# KeyInput_ABH.net
KiCad netlist of a schematic drawn in Altium Designer
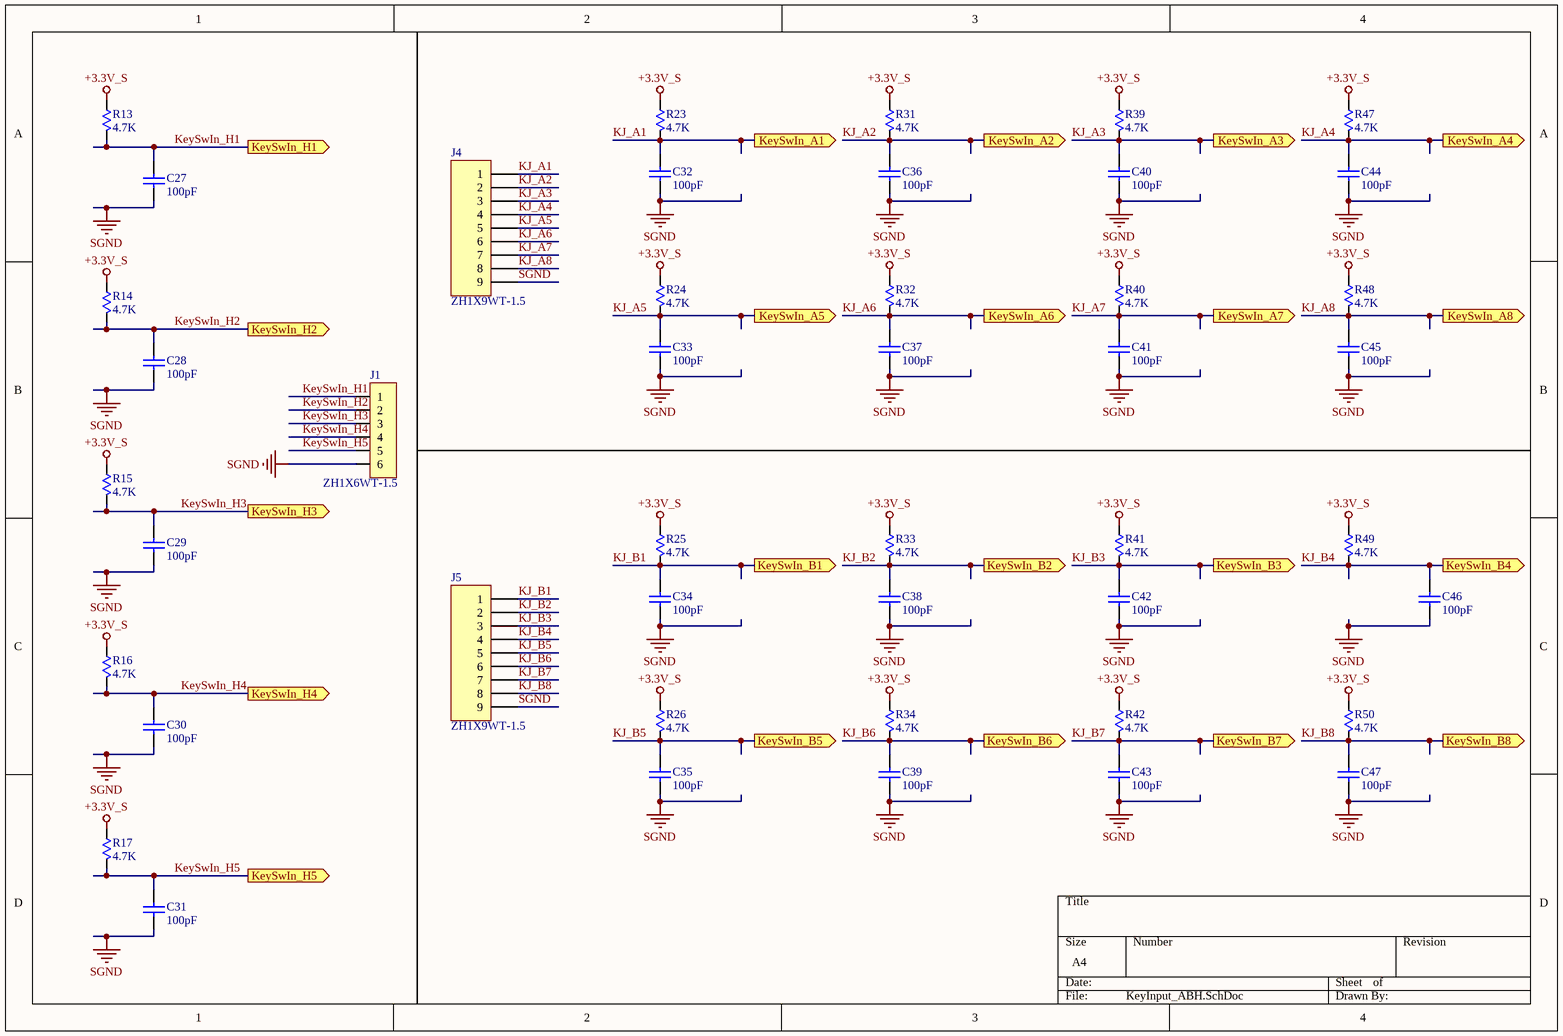
[diagram p0: KeyInput_ABH.SchDoc]

(export (version "E")
  (design (tool "Eeschema 10.0.6"))
  (components
    (comp (ref "C27")
      (value "100pF")
      (footprint "C0805")
      (description "Capacitor")
      (fields (field (name "PUBLISHER") "Altium Limited"))
      (libsource (lib "Miscellaneous Devices") (part "Cap"))
    )
    (comp (ref "C28")
      (value "100pF")
      (footprint "C0805")
      (description "Capacitor")
      (fields (field (name "PUBLISHER") "Altium Limited"))
      (libsource (lib "Miscellaneous Devices") (part "Cap"))
    )
    (comp (ref "C29")
      (value "100pF")
      (footprint "C0805")
      (description "Capacitor")
      (fields (field (name "PUBLISHER") "Altium Limited"))
      (libsource (lib "Miscellaneous Devices") (part "Cap"))
    )
    (comp (ref "C30")
      (value "100pF")
      (footprint "C0805")
      (description "Capacitor")
      (fields (field (name "PUBLISHER") "Altium Limited"))
      (libsource (lib "Miscellaneous Devices") (part "Cap"))
    )
    (comp (ref "C31")
      (value "100pF")
      (footprint "C0805")
      (description "Capacitor")
      (fields (field (name "PUBLISHER") "Altium Limited"))
      (libsource (lib "Miscellaneous Devices") (part "Cap"))
    )
    (comp (ref "C32")
      (value "100pF")
      (footprint "C0805")
      (description "Capacitor")
      (fields (field (name "PUBLISHER") "Altium Limited"))
      (libsource (lib "Miscellaneous Devices") (part "Cap"))
    )
    (comp (ref "C33")
      (value "100pF")
      (footprint "C0805")
      (description "Capacitor")
      (fields (field (name "PUBLISHER") "Altium Limited"))
      (libsource (lib "Miscellaneous Devices") (part "Cap"))
    )
    (comp (ref "C34")
      (value "100pF")
      (footprint "C0805")
      (description "Capacitor")
      (fields (field (name "PUBLISHER") "Altium Limited"))
      (libsource (lib "Miscellaneous Devices") (part "Cap"))
    )
    (comp (ref "C35")
      (value "100pF")
      (footprint "C0805")
      (description "Capacitor")
      (fields (field (name "PUBLISHER") "Altium Limited"))
      (libsource (lib "Miscellaneous Devices") (part "Cap"))
    )
    (comp (ref "C36")
      (value "100pF")
      (footprint "C0805")
      (description "Capacitor")
      (fields (field (name "PUBLISHER") "Altium Limited"))
      (libsource (lib "Miscellaneous Devices") (part "Cap"))
    )
    (comp (ref "C37")
      (value "100pF")
      (footprint "C0805")
      (description "Capacitor")
      (fields (field (name "PUBLISHER") "Altium Limited"))
      (libsource (lib "Miscellaneous Devices") (part "Cap"))
    )
    (comp (ref "C38")
      (value "100pF")
      (footprint "C0805")
      (description "Capacitor")
      (fields (field (name "PUBLISHER") "Altium Limited"))
      (libsource (lib "Miscellaneous Devices") (part "Cap"))
    )
    (comp (ref "C39")
      (value "100pF")
      (footprint "C0805")
      (description "Capacitor")
      (fields (field (name "PUBLISHER") "Altium Limited"))
      (libsource (lib "Miscellaneous Devices") (part "Cap"))
    )
    (comp (ref "C40")
      (value "100pF")
      (footprint "C0805")
      (description "Capacitor")
      (fields (field (name "PUBLISHER") "Altium Limited"))
      (libsource (lib "Miscellaneous Devices") (part "Cap"))
    )
    (comp (ref "C41")
      (value "100pF")
      (footprint "C0805")
      (description "Capacitor")
      (fields (field (name "PUBLISHER") "Altium Limited"))
      (libsource (lib "Miscellaneous Devices") (part "Cap"))
    )
    (comp (ref "C42")
      (value "100pF")
      (footprint "C0805")
      (description "Capacitor")
      (fields (field (name "PUBLISHER") "Altium Limited"))
      (libsource (lib "Miscellaneous Devices") (part "Cap"))
    )
    (comp (ref "C43")
      (value "100pF")
      (footprint "C0805")
      (description "Capacitor")
      (fields (field (name "PUBLISHER") "Altium Limited"))
      (libsource (lib "Miscellaneous Devices") (part "Cap"))
    )
    (comp (ref "C44")
      (value "100pF")
      (footprint "C0805")
      (description "Capacitor")
      (fields (field (name "PUBLISHER") "Altium Limited"))
      (libsource (lib "Miscellaneous Devices") (part "Cap"))
    )
    (comp (ref "C45")
      (value "100pF")
      (footprint "C0805")
      (description "Capacitor")
      (fields (field (name "PUBLISHER") "Altium Limited"))
      (libsource (lib "Miscellaneous Devices") (part "Cap"))
    )
    (comp (ref "C46")
      (value "100pF")
      (footprint "C0805")
      (description "Capacitor")
      (fields (field (name "PUBLISHER") "Altium Limited"))
      (libsource (lib "Miscellaneous Devices") (part "Cap"))
    )
    (comp (ref "C47")
      (value "100pF")
      (footprint "C0805")
      (description "Capacitor")
      (fields (field (name "PUBLISHER") "Altium Limited"))
      (libsource (lib "Miscellaneous Devices") (part "Cap"))
    )
    (comp (ref "J1")
      (value "ZH1X6WT-1.5")
      (footprint "ZH1X6WT-1.5")
      (libsource (lib "Connector Class") (part "HEADER1X6"))
    )
    (comp (ref "J4")
      (value "ZH1X9WT-1.5")
      (footprint "ZH1X9WT-1.5")
      (description "Header, 9-Pin")
      (fields (field (name "PUBLISHER") "Altium Limited"))
      (libsource (lib "Miscellaneous Connectors") (part "Header 9"))
    )
    (comp (ref "J5")
      (value "ZH1X9WT-1.5")
      (footprint "ZH1X9WT-1.5")
      (description "Header, 9-Pin")
      (fields (field (name "PUBLISHER") "Altium Limited"))
      (libsource (lib "Miscellaneous Connectors") (part "Header 9"))
    )
    (comp (ref "R13")
      (value "4.7K")
      (footprint "R0805")
      (description "Resistor")
      (fields (field (name "PUBLISHER") "Altium Limited"))
      (libsource (lib "Passive Components Class") (part "RES"))
    )
    (comp (ref "R14")
      (value "4.7K")
      (footprint "R0805")
      (description "Resistor")
      (fields (field (name "PUBLISHER") "Altium Limited"))
      (libsource (lib "Passive Components Class") (part "RES"))
    )
    (comp (ref "R15")
      (value "4.7K")
      (footprint "R0805")
      (description "Resistor")
      (fields (field (name "PUBLISHER") "Altium Limited"))
      (libsource (lib "Passive Components Class") (part "RES"))
    )
    (comp (ref "R16")
      (value "4.7K")
      (footprint "R0805")
      (description "Resistor")
      (fields (field (name "PUBLISHER") "Altium Limited"))
      (libsource (lib "Passive Components Class") (part "RES"))
    )
    (comp (ref "R17")
      (value "4.7K")
      (footprint "R0805")
      (description "Resistor")
      (fields (field (name "PUBLISHER") "Altium Limited"))
      (libsource (lib "Passive Components Class") (part "RES"))
    )
    (comp (ref "R23")
      (value "4.7K")
      (footprint "R0805")
      (description "Resistor")
      (fields (field (name "PUBLISHER") "Altium Limited"))
      (libsource (lib "Passive Components Class") (part "RES"))
    )
    (comp (ref "R24")
      (value "4.7K")
      (footprint "R0805")
      (description "Resistor")
      (fields (field (name "PUBLISHER") "Altium Limited"))
      (libsource (lib "Passive Components Class") (part "RES"))
    )
    (comp (ref "R25")
      (value "4.7K")
      (footprint "R0805")
      (description "Resistor")
      (fields (field (name "PUBLISHER") "Altium Limited"))
      (libsource (lib "Passive Components Class") (part "RES"))
    )
    (comp (ref "R26")
      (value "4.7K")
      (footprint "R0805")
      (description "Resistor")
      (fields (field (name "PUBLISHER") "Altium Limited"))
      (libsource (lib "Passive Components Class") (part "RES"))
    )
    (comp (ref "R31")
      (value "4.7K")
      (footprint "R0805")
      (description "Resistor")
      (fields (field (name "PUBLISHER") "Altium Limited"))
      (libsource (lib "Passive Components Class") (part "RES"))
    )
    (comp (ref "R32")
      (value "4.7K")
      (footprint "R0805")
      (description "Resistor")
      (fields (field (name "PUBLISHER") "Altium Limited"))
      (libsource (lib "Passive Components Class") (part "RES"))
    )
    (comp (ref "R33")
      (value "4.7K")
      (footprint "R0805")
      (description "Resistor")
      (fields (field (name "PUBLISHER") "Altium Limited"))
      (libsource (lib "Passive Components Class") (part "RES"))
    )
    (comp (ref "R34")
      (value "4.7K")
      (footprint "R0805")
      (description "Resistor")
      (fields (field (name "PUBLISHER") "Altium Limited"))
      (libsource (lib "Passive Components Class") (part "RES"))
    )
    (comp (ref "R39")
      (value "4.7K")
      (footprint "R0805")
      (description "Resistor")
      (fields (field (name "PUBLISHER") "Altium Limited"))
      (libsource (lib "Passive Components Class") (part "RES"))
    )
    (comp (ref "R40")
      (value "4.7K")
      (footprint "R0805")
      (description "Resistor")
      (fields (field (name "PUBLISHER") "Altium Limited"))
      (libsource (lib "Passive Components Class") (part "RES"))
    )
    (comp (ref "R41")
      (value "4.7K")
      (footprint "R0805")
      (description "Resistor")
      (fields (field (name "PUBLISHER") "Altium Limited"))
      (libsource (lib "Passive Components Class") (part "RES"))
    )
    (comp (ref "R42")
      (value "4.7K")
      (footprint "R0805")
      (description "Resistor")
      (fields (field (name "PUBLISHER") "Altium Limited"))
      (libsource (lib "Passive Components Class") (part "RES"))
    )
    (comp (ref "R47")
      (value "4.7K")
      (footprint "R0805")
      (description "Resistor")
      (fields (field (name "PUBLISHER") "Altium Limited"))
      (libsource (lib "Passive Components Class") (part "RES"))
    )
    (comp (ref "R48")
      (value "4.7K")
      (footprint "R0805")
      (description "Resistor")
      (fields (field (name "PUBLISHER") "Altium Limited"))
      (libsource (lib "Passive Components Class") (part "RES"))
    )
    (comp (ref "R49")
      (value "4.7K")
      (footprint "R0805")
      (description "Resistor")
      (fields (field (name "PUBLISHER") "Altium Limited"))
      (libsource (lib "Passive Components Class") (part "RES"))
    )
    (comp (ref "R50")
      (value "4.7K")
      (footprint "R0805")
      (description "Resistor")
      (fields (field (name "PUBLISHER") "Altium Limited"))
      (libsource (lib "Passive Components Class") (part "RES"))
    )
  )
  (nets
    (net (code "1") (name "+3.3V_S") (class "Default")
      (node (ref "R13") (pin "2") (pinfunction "2_2") (pintype "passive"))
      (node (ref "R14") (pin "2") (pinfunction "2_2") (pintype "passive"))
      (node (ref "R15") (pin "2") (pinfunction "2_2") (pintype "passive"))
      (node (ref "R16") (pin "2") (pinfunction "2_2") (pintype "passive"))
      (node (ref "R17") (pin "2") (pinfunction "2_2") (pintype "passive"))
      (node (ref "R23") (pin "2") (pinfunction "2_2") (pintype "passive"))
      (node (ref "R24") (pin "2") (pinfunction "2_2") (pintype "passive"))
      (node (ref "R25") (pin "2") (pinfunction "2_2") (pintype "passive"))
      (node (ref "R26") (pin "2") (pinfunction "2_2") (pintype "passive"))
      (node (ref "R31") (pin "2") (pinfunction "2_2") (pintype "passive"))
      (node (ref "R32") (pin "2") (pinfunction "2_2") (pintype "passive"))
      (node (ref "R33") (pin "2") (pinfunction "2_2") (pintype "passive"))
      (node (ref "R34") (pin "2") (pinfunction "2_2") (pintype "passive"))
      (node (ref "R39") (pin "2") (pinfunction "2_2") (pintype "passive"))
      (node (ref "R40") (pin "2") (pinfunction "2_2") (pintype "passive"))
      (node (ref "R41") (pin "2") (pinfunction "2_2") (pintype "passive"))
      (node (ref "R42") (pin "2") (pinfunction "2_2") (pintype "passive"))
      (node (ref "R47") (pin "2") (pinfunction "2_2") (pintype "passive"))
      (node (ref "R48") (pin "2") (pinfunction "2_2") (pintype "passive"))
      (node (ref "R49") (pin "2") (pinfunction "2_2") (pintype "passive"))
      (node (ref "R50") (pin "2") (pinfunction "2_2") (pintype "passive"))
    )
    (net (code "2") (name "/KJ_A1") (class "Default")
      (node (ref "C32") (pin "1") (pinfunction "1_1") (pintype "passive"))
      (node (ref "J4") (pin "1") (pinfunction "1_1") (pintype "passive"))
      (node (ref "R23") (pin "1") (pinfunction "1_1") (pintype "passive"))
    )
    (net (code "3") (name "/KJ_A2") (class "Default")
      (node (ref "C36") (pin "1") (pinfunction "1_1") (pintype "passive"))
      (node (ref "J4") (pin "2") (pinfunction "2_2") (pintype "passive"))
      (node (ref "R31") (pin "1") (pinfunction "1_1") (pintype "passive"))
    )
    (net (code "4") (name "/KJ_A3") (class "Default")
      (node (ref "C40") (pin "1") (pinfunction "1_1") (pintype "passive"))
      (node (ref "J4") (pin "3") (pinfunction "3_3") (pintype "passive"))
      (node (ref "R39") (pin "1") (pinfunction "1_1") (pintype "passive"))
    )
    (net (code "5") (name "/KJ_A4") (class "Default")
      (node (ref "C44") (pin "1") (pinfunction "1_1") (pintype "passive"))
      (node (ref "J4") (pin "4") (pinfunction "4_4") (pintype "passive"))
      (node (ref "R47") (pin "1") (pinfunction "1_1") (pintype "passive"))
    )
    (net (code "6") (name "/KJ_A5") (class "Default")
      (node (ref "C33") (pin "1") (pinfunction "1_1") (pintype "passive"))
      (node (ref "J4") (pin "5") (pinfunction "5_5") (pintype "passive"))
      (node (ref "R24") (pin "1") (pinfunction "1_1") (pintype "passive"))
    )
    (net (code "7") (name "/KJ_A6") (class "Default")
      (node (ref "C37") (pin "1") (pinfunction "1_1") (pintype "passive"))
      (node (ref "J4") (pin "6") (pinfunction "6_6") (pintype "passive"))
      (node (ref "R32") (pin "1") (pinfunction "1_1") (pintype "passive"))
    )
    (net (code "8") (name "/KJ_A7") (class "Default")
      (node (ref "C41") (pin "1") (pinfunction "1_1") (pintype "passive"))
      (node (ref "J4") (pin "7") (pinfunction "7_7") (pintype "passive"))
      (node (ref "R40") (pin "1") (pinfunction "1_1") (pintype "passive"))
    )
    (net (code "9") (name "/KJ_A8") (class "Default")
      (node (ref "C45") (pin "1") (pinfunction "1_1") (pintype "passive"))
      (node (ref "J4") (pin "8") (pinfunction "8_8") (pintype "passive"))
      (node (ref "R48") (pin "1") (pinfunction "1_1") (pintype "passive"))
    )
    (net (code "10") (name "/KJ_B1") (class "Default")
      (node (ref "C34") (pin "1") (pinfunction "1_1") (pintype "passive"))
      (node (ref "J5") (pin "1") (pinfunction "1_1") (pintype "passive"))
      (node (ref "R25") (pin "1") (pinfunction "1_1") (pintype "passive"))
    )
    (net (code "11") (name "/KJ_B2") (class "Default")
      (node (ref "C38") (pin "1") (pinfunction "1_1") (pintype "passive"))
      (node (ref "J5") (pin "2") (pinfunction "2_2") (pintype "passive"))
      (node (ref "R33") (pin "1") (pinfunction "1_1") (pintype "passive"))
    )
    (net (code "12") (name "/KJ_B3") (class "Default")
      (node (ref "C42") (pin "1") (pinfunction "1_1") (pintype "passive"))
      (node (ref "J5") (pin "3") (pinfunction "3_3") (pintype "passive"))
      (node (ref "R41") (pin "1") (pinfunction "1_1") (pintype "passive"))
    )
    (net (code "13") (name "/KJ_B4") (class "Default")
      (node (ref "C46") (pin "1") (pinfunction "1_1") (pintype "passive"))
      (node (ref "J5") (pin "4") (pinfunction "4_4") (pintype "passive"))
      (node (ref "R49") (pin "1") (pinfunction "1_1") (pintype "passive"))
    )
    (net (code "14") (name "/KJ_B5") (class "Default")
      (node (ref "C35") (pin "1") (pinfunction "1_1") (pintype "passive"))
      (node (ref "J5") (pin "5") (pinfunction "5_5") (pintype "passive"))
      (node (ref "R26") (pin "1") (pinfunction "1_1") (pintype "passive"))
    )
    (net (code "15") (name "/KJ_B6") (class "Default")
      (node (ref "C39") (pin "1") (pinfunction "1_1") (pintype "passive"))
      (node (ref "J5") (pin "6") (pinfunction "6_6") (pintype "passive"))
      (node (ref "R34") (pin "1") (pinfunction "1_1") (pintype "passive"))
    )
    (net (code "16") (name "/KJ_B7") (class "Default")
      (node (ref "C43") (pin "1") (pinfunction "1_1") (pintype "passive"))
      (node (ref "J5") (pin "7") (pinfunction "7_7") (pintype "passive"))
      (node (ref "R42") (pin "1") (pinfunction "1_1") (pintype "passive"))
    )
    (net (code "17") (name "/KJ_B8") (class "Default")
      (node (ref "C47") (pin "1") (pinfunction "1_1") (pintype "passive"))
      (node (ref "J5") (pin "8") (pinfunction "8_8") (pintype "passive"))
      (node (ref "R50") (pin "1") (pinfunction "1_1") (pintype "passive"))
    )
    (net (code "18") (name "/KeySwIn_H1") (class "Default")
      (node (ref "C27") (pin "1") (pinfunction "1_1") (pintype "passive"))
      (node (ref "J1") (pin "1") (pinfunction "1_1") (pintype "passive"))
      (node (ref "R13") (pin "1") (pinfunction "1_1") (pintype "passive"))
    )
    (net (code "19") (name "/KeySwIn_H2") (class "Default")
      (node (ref "C28") (pin "1") (pinfunction "1_1") (pintype "passive"))
      (node (ref "J1") (pin "2") (pinfunction "2_2") (pintype "passive"))
      (node (ref "R14") (pin "1") (pinfunction "1_1") (pintype "passive"))
    )
    (net (code "20") (name "/KeySwIn_H3") (class "Default")
      (node (ref "C29") (pin "1") (pinfunction "1_1") (pintype "passive"))
      (node (ref "J1") (pin "3") (pinfunction "3_3") (pintype "passive"))
      (node (ref "R15") (pin "1") (pinfunction "1_1") (pintype "passive"))
    )
    (net (code "21") (name "/KeySwIn_H4") (class "Default")
      (node (ref "C30") (pin "1") (pinfunction "1_1") (pintype "passive"))
      (node (ref "J1") (pin "4") (pinfunction "4_4") (pintype "passive"))
      (node (ref "R16") (pin "1") (pinfunction "1_1") (pintype "passive"))
    )
    (net (code "22") (name "/KeySwIn_H5") (class "Default")
      (node (ref "C31") (pin "1") (pinfunction "1_1") (pintype "passive"))
      (node (ref "J1") (pin "5") (pinfunction "5_5") (pintype "passive"))
      (node (ref "R17") (pin "1") (pinfunction "1_1") (pintype "passive"))
    )
    (net (code "23") (name "SGND") (class "Default")
      (node (ref "C27") (pin "2") (pinfunction "2_2") (pintype "passive"))
      (node (ref "C28") (pin "2") (pinfunction "2_2") (pintype "passive"))
      (node (ref "C29") (pin "2") (pinfunction "2_2") (pintype "passive"))
      (node (ref "C30") (pin "2") (pinfunction "2_2") (pintype "passive"))
      (node (ref "C31") (pin "2") (pinfunction "2_2") (pintype "passive"))
      (node (ref "C32") (pin "2") (pinfunction "2_2") (pintype "passive"))
      (node (ref "C33") (pin "2") (pinfunction "2_2") (pintype "passive"))
      (node (ref "C34") (pin "2") (pinfunction "2_2") (pintype "passive"))
      (node (ref "C35") (pin "2") (pinfunction "2_2") (pintype "passive"))
      (node (ref "C36") (pin "2") (pinfunction "2_2") (pintype "passive"))
      (node (ref "C37") (pin "2") (pinfunction "2_2") (pintype "passive"))
      (node (ref "C38") (pin "2") (pinfunction "2_2") (pintype "passive"))
      (node (ref "C39") (pin "2") (pinfunction "2_2") (pintype "passive"))
      (node (ref "C40") (pin "2") (pinfunction "2_2") (pintype "passive"))
      (node (ref "C41") (pin "2") (pinfunction "2_2") (pintype "passive"))
      (node (ref "C42") (pin "2") (pinfunction "2_2") (pintype "passive"))
      (node (ref "C43") (pin "2") (pinfunction "2_2") (pintype "passive"))
      (node (ref "C44") (pin "2") (pinfunction "2_2") (pintype "passive"))
      (node (ref "C45") (pin "2") (pinfunction "2_2") (pintype "passive"))
      (node (ref "C46") (pin "2") (pinfunction "2_2") (pintype "passive"))
      (node (ref "C47") (pin "2") (pinfunction "2_2") (pintype "passive"))
      (node (ref "J1") (pin "6") (pinfunction "6_6") (pintype "passive"))
      (node (ref "J4") (pin "9") (pinfunction "9_9") (pintype "passive"))
      (node (ref "J5") (pin "9") (pinfunction "9_9") (pintype "passive"))
    )
  )
)
